# pclone-control.net
KiCad netlist of a schematic drawn in EAGLE
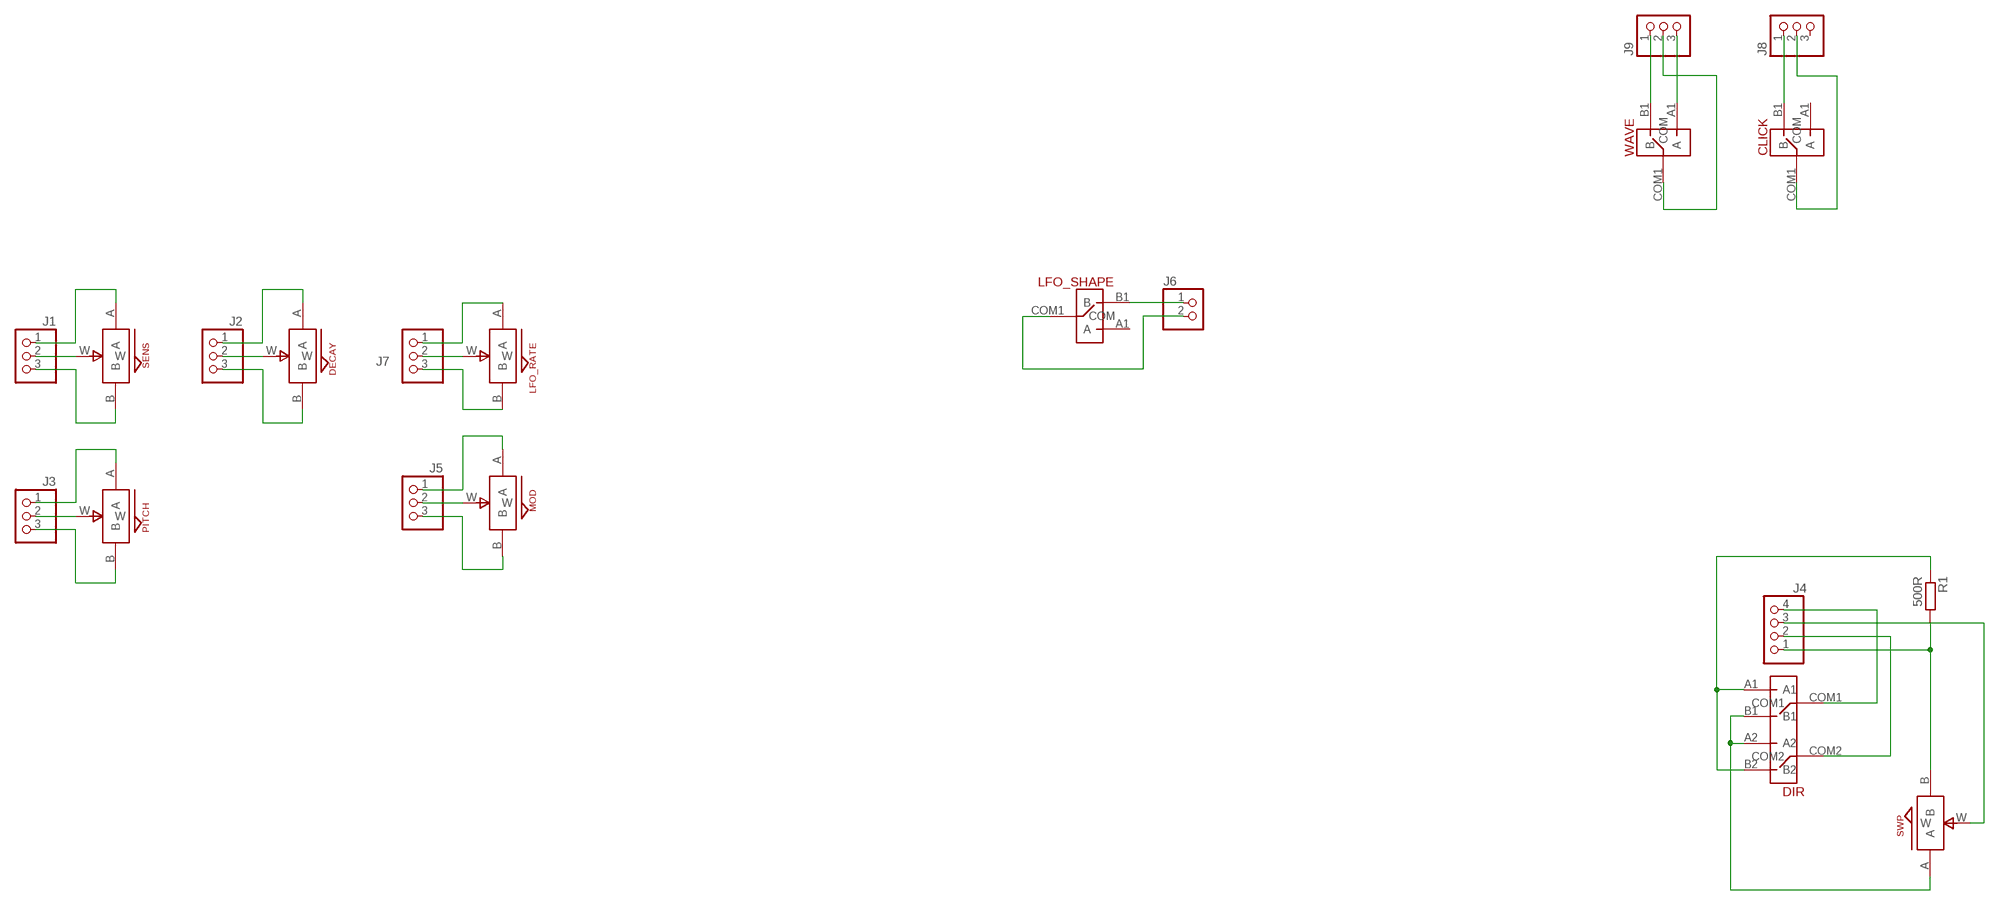
[diagram p0: schematic, sheet 1]

(export (version "E")
  (design (tool "Eeschema 10.0.6"))
  (components
    (comp (ref "CLICK")
      (value "SPDT_SW")
      (footprint "eagle-import:SPDT_SW")
      (libsource (lib "eagle-import") (part "SPDT_SW"))
    )
    (comp (ref "DECAY")
      (value "ALPS_POT_SMALL")
      (footprint "eagle-import:SMALL_ALPS_POT")
      (libsource (lib "eagle-import") (part "ALPS_POT_SMALL"))
    )
    (comp (ref "DIR")
      (value "DPDT_SW")
      (footprint "eagle-import:DPDT_SW")
      (libsource (lib "eagle-import") (part "DPDT_SW"))
    )
    (comp (ref "J1")
      (value "PINHD-1X3")
      (footprint "eagle-import:1X03")
      (libsource (lib "eagle-import") (part "PINHD-1X3"))
    )
    (comp (ref "J2")
      (value "PINHD-1X3")
      (footprint "eagle-import:1X03")
      (libsource (lib "eagle-import") (part "PINHD-1X3"))
    )
    (comp (ref "J3")
      (value "PINHD-1X3")
      (footprint "eagle-import:1X03")
      (libsource (lib "eagle-import") (part "PINHD-1X3"))
    )
    (comp (ref "J4")
      (value "PINHD-1X4")
      (footprint "eagle-import:1X04")
      (libsource (lib "eagle-import") (part "PINHD-1X4"))
    )
    (comp (ref "J5")
      (value "PINHD-1X3")
      (footprint "eagle-import:1X03")
      (libsource (lib "eagle-import") (part "PINHD-1X3"))
    )
    (comp (ref "J6")
      (value "PINHD-1X2")
      (footprint "eagle-import:1X02")
      (libsource (lib "eagle-import") (part "PINHD-1X2"))
    )
    (comp (ref "J7")
      (value "PINHD-1X3")
      (footprint "eagle-import:1X03")
      (libsource (lib "eagle-import") (part "PINHD-1X3"))
    )
    (comp (ref "J8")
      (value "PINHD-1X3")
      (footprint "eagle-import:1X03")
      (libsource (lib "eagle-import") (part "PINHD-1X3"))
    )
    (comp (ref "J9")
      (value "PINHD-1X3")
      (footprint "eagle-import:1X03")
      (libsource (lib "eagle-import") (part "PINHD-1X3"))
    )
    (comp (ref "LFO_RATE")
      (value "ALPS_POT_SMALL")
      (footprint "eagle-import:SMALL_ALPS_POT")
      (libsource (lib "eagle-import") (part "ALPS_POT_SMALL"))
    )
    (comp (ref "LFO_SHAPE")
      (value "SPDT_SW")
      (footprint "eagle-import:SPDT_SW")
      (libsource (lib "eagle-import") (part "SPDT_SW"))
    )
    (comp (ref "MOD")
      (value "ALPS_POT_SMALL")
      (footprint "eagle-import:SMALL_ALPS_POT")
      (libsource (lib "eagle-import") (part "ALPS_POT_SMALL"))
    )
    (comp (ref "PITCH")
      (value "ALPS_POT_SMALL")
      (footprint "eagle-import:SMALL_ALPS_POT")
      (libsource (lib "eagle-import") (part "ALPS_POT_SMALL"))
    )
    (comp (ref "R1")
      (value "500R")
      (footprint "eagle-import:0207_7")
      (libsource (lib "eagle-import") (part "R-EU_0207/7"))
    )
    (comp (ref "SENS")
      (value "ALPS_POT_SMALL")
      (footprint "eagle-import:SMALL_ALPS_POT")
      (libsource (lib "eagle-import") (part "ALPS_POT_SMALL"))
    )
    (comp (ref "SWP")
      (value "ALPS_POT_SMALL")
      (footprint "eagle-import:SMALL_ALPS_POT")
      (libsource (lib "eagle-import") (part "ALPS_POT_SMALL"))
    )
    (comp (ref "WAVE")
      (value "SPDT_SW")
      (footprint "eagle-import:SPDT_SW")
      (libsource (lib "eagle-import") (part "SPDT_SW"))
    )
  )
  (nets
    (net (code "1") (name "Net-(CLICK-B)") (class "Default")
      (node (ref "CLICK") (pin "B1") (pinfunction "B_B1") (pintype "bidirectional"))
      (node (ref "J8") (pin "1") (pinfunction "1_1") (pintype "passive"))
    )
    (net (code "2") (name "Net-(CLICK-COM)") (class "Default")
      (node (ref "CLICK") (pin "COM1") (pinfunction "COM_COM1") (pintype "bidirectional"))
      (node (ref "J8") (pin "2") (pinfunction "2_2") (pintype "passive"))
    )
    (net (code "3") (name "Net-(DECAY-PadA)") (class "Default")
      (node (ref "DECAY") (pin "A") (pinfunction "A_A") (pintype "bidirectional"))
      (node (ref "J2") (pin "1") (pinfunction "1_1") (pintype "passive"))
    )
    (net (code "4") (name "Net-(DECAY-PadB)") (class "Default")
      (node (ref "DECAY") (pin "B") (pinfunction "B_B") (pintype "bidirectional"))
      (node (ref "J2") (pin "3") (pinfunction "3_3") (pintype "passive"))
    )
    (net (code "5") (name "Net-(DECAY-PadW)") (class "Default")
      (node (ref "DECAY") (pin "W") (pinfunction "W_W") (pintype "bidirectional"))
      (node (ref "J2") (pin "2") (pinfunction "2_2") (pintype "passive"))
    )
    (net (code "6") (name "Net-(DIR-PadA1)") (class "Default")
      (node (ref "DIR") (pin "A1") (pinfunction "A1_A1") (pintype "bidirectional"))
      (node (ref "DIR") (pin "B2") (pinfunction "B2_B2") (pintype "bidirectional"))
      (node (ref "R1") (pin "1") (pinfunction "1_1") (pintype "passive"))
    )
    (net (code "7") (name "Net-(DIR-PadA2)") (class "Default")
      (node (ref "DIR") (pin "A2") (pinfunction "A2_A2") (pintype "bidirectional"))
      (node (ref "DIR") (pin "B1") (pinfunction "B1_B1") (pintype "bidirectional"))
      (node (ref "SWP") (pin "A") (pinfunction "A_A") (pintype "bidirectional"))
    )
    (net (code "8") (name "Net-(DIR-PadCOM1)") (class "Default")
      (node (ref "DIR") (pin "COM1") (pinfunction "COM1_COM1") (pintype "bidirectional"))
      (node (ref "J4") (pin "4") (pinfunction "4_4") (pintype "passive"))
    )
    (net (code "9") (name "Net-(DIR-PadCOM2)") (class "Default")
      (node (ref "DIR") (pin "COM2") (pinfunction "COM2_COM2") (pintype "bidirectional"))
      (node (ref "J4") (pin "2") (pinfunction "2_2") (pintype "passive"))
    )
    (net (code "10") (name "Net-(J1-Pad1)") (class "Default")
      (node (ref "J1") (pin "1") (pinfunction "1_1") (pintype "passive"))
      (node (ref "SENS") (pin "A") (pinfunction "A_A") (pintype "bidirectional"))
    )
    (net (code "11") (name "Net-(J1-Pad2)") (class "Default")
      (node (ref "J1") (pin "2") (pinfunction "2_2") (pintype "passive"))
      (node (ref "SENS") (pin "W") (pinfunction "W_W") (pintype "bidirectional"))
    )
    (net (code "12") (name "Net-(J1-Pad3)") (class "Default")
      (node (ref "J1") (pin "3") (pinfunction "3_3") (pintype "passive"))
      (node (ref "SENS") (pin "B") (pinfunction "B_B") (pintype "bidirectional"))
    )
    (net (code "13") (name "Net-(J3-Pad1)") (class "Default")
      (node (ref "J3") (pin "1") (pinfunction "1_1") (pintype "passive"))
      (node (ref "PITCH") (pin "A") (pinfunction "A_A") (pintype "bidirectional"))
    )
    (net (code "14") (name "Net-(J3-Pad2)") (class "Default")
      (node (ref "J3") (pin "2") (pinfunction "2_2") (pintype "passive"))
      (node (ref "PITCH") (pin "W") (pinfunction "W_W") (pintype "bidirectional"))
    )
    (net (code "15") (name "Net-(J3-Pad3)") (class "Default")
      (node (ref "J3") (pin "3") (pinfunction "3_3") (pintype "passive"))
      (node (ref "PITCH") (pin "B") (pinfunction "B_B") (pintype "bidirectional"))
    )
    (net (code "16") (name "Net-(J4-Pad1)") (class "Default")
      (node (ref "J4") (pin "1") (pinfunction "1_1") (pintype "passive"))
      (node (ref "R1") (pin "2") (pinfunction "2_2") (pintype "passive"))
      (node (ref "SWP") (pin "B") (pinfunction "B_B") (pintype "bidirectional"))
    )
    (net (code "17") (name "Net-(J4-Pad3)") (class "Default")
      (node (ref "J4") (pin "3") (pinfunction "3_3") (pintype "passive"))
      (node (ref "SWP") (pin "W") (pinfunction "W_W") (pintype "bidirectional"))
    )
    (net (code "18") (name "Net-(J5-Pad1)") (class "Default")
      (node (ref "J5") (pin "1") (pinfunction "1_1") (pintype "passive"))
      (node (ref "MOD") (pin "A") (pinfunction "A_A") (pintype "bidirectional"))
    )
    (net (code "19") (name "Net-(J5-Pad2)") (class "Default")
      (node (ref "J5") (pin "2") (pinfunction "2_2") (pintype "passive"))
      (node (ref "MOD") (pin "W") (pinfunction "W_W") (pintype "bidirectional"))
    )
    (net (code "20") (name "Net-(J5-Pad3)") (class "Default")
      (node (ref "J5") (pin "3") (pinfunction "3_3") (pintype "passive"))
      (node (ref "MOD") (pin "B") (pinfunction "B_B") (pintype "bidirectional"))
    )
    (net (code "21") (name "Net-(J7-Pad1)") (class "Default")
      (node (ref "J7") (pin "1") (pinfunction "1_1") (pintype "passive"))
      (node (ref "LFO_RATE") (pin "A") (pinfunction "A_A") (pintype "bidirectional"))
    )
    (net (code "22") (name "Net-(J7-Pad2)") (class "Default")
      (node (ref "J7") (pin "2") (pinfunction "2_2") (pintype "passive"))
      (node (ref "LFO_RATE") (pin "W") (pinfunction "W_W") (pintype "bidirectional"))
    )
    (net (code "23") (name "Net-(J7-Pad3)") (class "Default")
      (node (ref "J7") (pin "3") (pinfunction "3_3") (pintype "passive"))
      (node (ref "LFO_RATE") (pin "B") (pinfunction "B_B") (pintype "bidirectional"))
    )
    (net (code "24") (name "Net-(LFO_SHAPE-B)") (class "Default")
      (node (ref "J6") (pin "1") (pinfunction "1_1") (pintype "passive"))
      (node (ref "LFO_SHAPE") (pin "B1") (pinfunction "B_B1") (pintype "bidirectional"))
    )
    (net (code "25") (name "Net-(LFO_SHAPE-COM)") (class "Default")
      (node (ref "J6") (pin "2") (pinfunction "2_2") (pintype "passive"))
      (node (ref "LFO_SHAPE") (pin "COM1") (pinfunction "COM_COM1") (pintype "bidirectional"))
    )
    (net (code "26") (name "Net-(WAVE-A)") (class "Default")
      (node (ref "J9") (pin "3") (pinfunction "3_3") (pintype "passive"))
      (node (ref "WAVE") (pin "A1") (pinfunction "A_A1") (pintype "bidirectional"))
    )
    (net (code "27") (name "Net-(WAVE-B)") (class "Default")
      (node (ref "J9") (pin "1") (pinfunction "1_1") (pintype "passive"))
      (node (ref "WAVE") (pin "B1") (pinfunction "B_B1") (pintype "bidirectional"))
    )
    (net (code "28") (name "Net-(WAVE-COM)") (class "Default")
      (node (ref "J9") (pin "2") (pinfunction "2_2") (pintype "passive"))
      (node (ref "WAVE") (pin "COM1") (pinfunction "COM_COM1") (pintype "bidirectional"))
    )
    (net (code "29") (name "unconnected-(CLICK-A-PadA1)") (class "Default")
      (node (ref "CLICK") (pin "A1") (pinfunction "A_A1") (pintype "bidirectional"))
    )
    (net (code "30") (name "unconnected-(J8-Pad3)") (class "Default")
      (node (ref "J8") (pin "3") (pinfunction "3_3") (pintype "passive"))
    )
    (net (code "31") (name "unconnected-(LFO_SHAPE-A-PadA1)") (class "Default")
      (node (ref "LFO_SHAPE") (pin "A1") (pinfunction "A_A1") (pintype "bidirectional"))
    )
  )
)
